# ninjaNIRS_TriggerBox_Rev1a.net
KiCad netlist of a schematic drawn in EAGLE
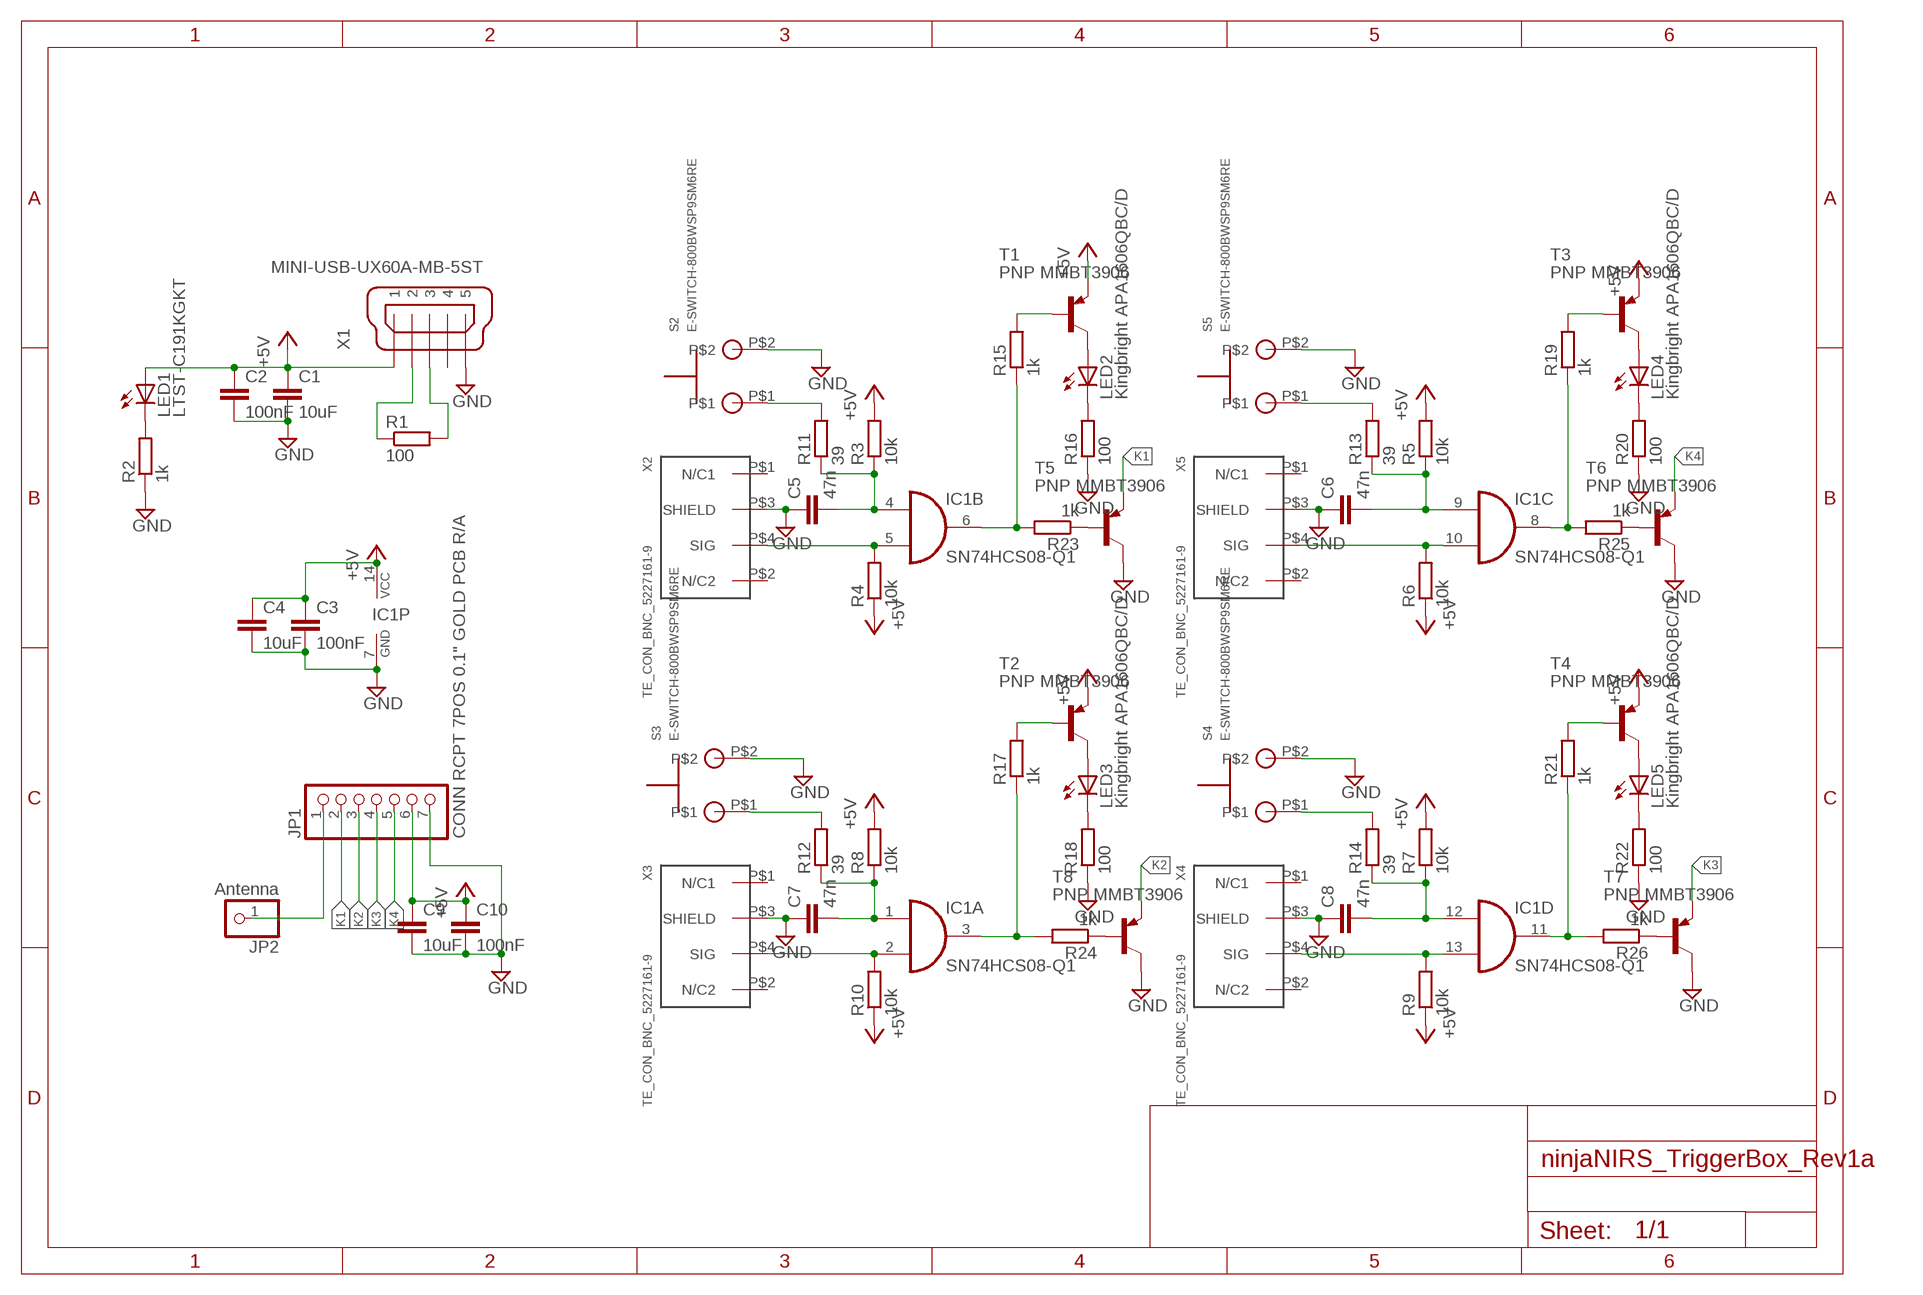
[diagram p0: schematic, sheet 1]

(export (version "E")
  (design (tool "Eeschema 10.0.6"))
  (components
    (comp (ref "C1")
      (value "10uF")
      (footprint "eagle-import:C1210")
      (libsource (lib "eagle-import") (part "C-EUC1210"))
    )
    (comp (ref "C2")
      (value "100nF")
      (footprint "eagle-import:C0805")
      (libsource (lib "eagle-import") (part "C-EUC0805"))
    )
    (comp (ref "C3")
      (value "100nF")
      (footprint "eagle-import:C0805")
      (libsource (lib "eagle-import") (part "C-EUC0805"))
    )
    (comp (ref "C4")
      (value "10uF")
      (footprint "eagle-import:C1210")
      (libsource (lib "eagle-import") (part "C-EUC1210"))
    )
    (comp (ref "C5")
      (value "47n")
      (footprint "eagle-import:C0805")
      (libsource (lib "eagle-import") (part "C-EUC0805"))
    )
    (comp (ref "C6")
      (value "47n")
      (footprint "eagle-import:C0805")
      (libsource (lib "eagle-import") (part "C-EUC0805"))
    )
    (comp (ref "C7")
      (value "47n")
      (footprint "eagle-import:C0805")
      (libsource (lib "eagle-import") (part "C-EUC0805"))
    )
    (comp (ref "C8")
      (value "47n")
      (footprint "eagle-import:C0805")
      (libsource (lib "eagle-import") (part "C-EUC0805"))
    )
    (comp (ref "C9")
      (value "10uF")
      (footprint "eagle-import:C1210")
      (libsource (lib "eagle-import") (part "C-EUC1210"))
    )
    (comp (ref "C10")
      (value "100nF")
      (footprint "eagle-import:C0805")
      (libsource (lib "eagle-import") (part "C-EUC0805"))
    )
    (comp (ref "IC1")
      (value "SN74HCS08-Q1")
      (footprint "eagle-import:SO14")
      (libsource (lib "eagle-import") (part "7408DHC"))
    )
    (comp (ref "JP1")
      (value "CONN RCPT 7POS 0.1\" GOLD PCB R/A")
      (footprint "eagle-import:1X07_90")
      (libsource (lib "eagle-import") (part "PINHD-1X7/90"))
    )
    (comp (ref "JP2")
      (value "Antenna")
      (footprint "eagle-import:1X01")
      (libsource (lib "eagle-import") (part "PINHD-1X1"))
    )
    (comp (ref "LED1")
      (value "LTST-C191KGKT")
      (footprint "eagle-import:CHIPLED_0603")
      (libsource (lib "eagle-import") (part "LEDCHIPLED_0603"))
    )
    (comp (ref "LED2")
      (value "Kingbright APA1606QBC/D")
      (footprint "eagle-import:CHIP-LED0603")
      (libsource (lib "eagle-import") (part "LEDCHIP-LED0603"))
    )
    (comp (ref "LED3")
      (value "Kingbright APA1606QBC/D")
      (footprint "eagle-import:CHIP-LED0603")
      (libsource (lib "eagle-import") (part "LEDCHIP-LED0603"))
    )
    (comp (ref "LED4")
      (value "Kingbright APA1606QBC/D")
      (footprint "eagle-import:CHIP-LED0603")
      (libsource (lib "eagle-import") (part "LEDCHIP-LED0603"))
    )
    (comp (ref "LED5")
      (value "Kingbright APA1606QBC/D")
      (footprint "eagle-import:CHIP-LED0603")
      (libsource (lib "eagle-import") (part "LEDCHIP-LED0603"))
    )
    (comp (ref "R1")
      (value "100")
      (footprint "eagle-import:R1206")
      (libsource (lib "eagle-import") (part "R-EU_R1206"))
    )
    (comp (ref "R2")
      (value "1k")
      (footprint "eagle-import:R1206")
      (libsource (lib "eagle-import") (part "R-EU_R1206"))
    )
    (comp (ref "R3")
      (value "10k")
      (footprint "eagle-import:R1206")
      (libsource (lib "eagle-import") (part "R-EU_R1206"))
    )
    (comp (ref "R4")
      (value "10k")
      (footprint "eagle-import:R1206")
      (libsource (lib "eagle-import") (part "R-EU_R1206"))
    )
    (comp (ref "R5")
      (value "10k")
      (footprint "eagle-import:R1206")
      (libsource (lib "eagle-import") (part "R-EU_R1206"))
    )
    (comp (ref "R6")
      (value "10k")
      (footprint "eagle-import:R1206")
      (libsource (lib "eagle-import") (part "R-EU_R1206"))
    )
    (comp (ref "R7")
      (value "10k")
      (footprint "eagle-import:R1206")
      (libsource (lib "eagle-import") (part "R-EU_R1206"))
    )
    (comp (ref "R8")
      (value "10k")
      (footprint "eagle-import:R1206")
      (libsource (lib "eagle-import") (part "R-EU_R1206"))
    )
    (comp (ref "R9")
      (value "10k")
      (footprint "eagle-import:R1206")
      (libsource (lib "eagle-import") (part "R-EU_R1206"))
    )
    (comp (ref "R10")
      (value "10k")
      (footprint "eagle-import:R1206")
      (libsource (lib "eagle-import") (part "R-EU_R1206"))
    )
    (comp (ref "R11")
      (value "39")
      (footprint "eagle-import:R1206")
      (libsource (lib "eagle-import") (part "R-EU_R1206"))
    )
    (comp (ref "R12")
      (value "39")
      (footprint "eagle-import:R1206")
      (libsource (lib "eagle-import") (part "R-EU_R1206"))
    )
    (comp (ref "R13")
      (value "39")
      (footprint "eagle-import:R1206")
      (libsource (lib "eagle-import") (part "R-EU_R1206"))
    )
    (comp (ref "R14")
      (value "39")
      (footprint "eagle-import:R1206")
      (libsource (lib "eagle-import") (part "R-EU_R1206"))
    )
    (comp (ref "R15")
      (value "1k")
      (footprint "eagle-import:R1206")
      (libsource (lib "eagle-import") (part "R-EU_R1206"))
    )
    (comp (ref "R16")
      (value "100")
      (footprint "eagle-import:R1206")
      (libsource (lib "eagle-import") (part "R-EU_R1206"))
    )
    (comp (ref "R17")
      (value "1k")
      (footprint "eagle-import:R1206")
      (libsource (lib "eagle-import") (part "R-EU_R1206"))
    )
    (comp (ref "R18")
      (value "100")
      (footprint "eagle-import:R1206")
      (libsource (lib "eagle-import") (part "R-EU_R1206"))
    )
    (comp (ref "R19")
      (value "1k")
      (footprint "eagle-import:R1206")
      (libsource (lib "eagle-import") (part "R-EU_R1206"))
    )
    (comp (ref "R20")
      (value "100")
      (footprint "eagle-import:R1206")
      (libsource (lib "eagle-import") (part "R-EU_R1206"))
    )
    (comp (ref "R21")
      (value "1k")
      (footprint "eagle-import:R1206")
      (libsource (lib "eagle-import") (part "R-EU_R1206"))
    )
    (comp (ref "R22")
      (value "100")
      (footprint "eagle-import:R1206")
      (libsource (lib "eagle-import") (part "R-EU_R1206"))
    )
    (comp (ref "R23")
      (value "1k")
      (footprint "eagle-import:R1206")
      (libsource (lib "eagle-import") (part "R-EU_R1206"))
    )
    (comp (ref "R24")
      (value "1k")
      (footprint "eagle-import:R1206")
      (libsource (lib "eagle-import") (part "R-EU_R1206"))
    )
    (comp (ref "R25")
      (value "1k")
      (footprint "eagle-import:R1206")
      (libsource (lib "eagle-import") (part "R-EU_R1206"))
    )
    (comp (ref "R26")
      (value "1k")
      (footprint "eagle-import:R1206")
      (libsource (lib "eagle-import") (part "R-EU_R1206"))
    )
    (comp (ref "S2")
      (value "E-SWITCH-800BWSP9SM6RE")
      (footprint "eagle-import:E-SWITCH_800BW")
      (libsource (lib "eagle-import") (part "E-SWITCH-800BWSP9SM6RE"))
    )
    (comp (ref "S3")
      (value "E-SWITCH-800BWSP9SM6RE")
      (footprint "eagle-import:E-SWITCH_800BW")
      (libsource (lib "eagle-import") (part "E-SWITCH-800BWSP9SM6RE"))
    )
    (comp (ref "S4")
      (value "E-SWITCH-800BWSP9SM6RE")
      (footprint "eagle-import:E-SWITCH_800BW")
      (libsource (lib "eagle-import") (part "E-SWITCH-800BWSP9SM6RE"))
    )
    (comp (ref "S5")
      (value "E-SWITCH-800BWSP9SM6RE")
      (footprint "eagle-import:E-SWITCH_800BW")
      (libsource (lib "eagle-import") (part "E-SWITCH-800BWSP9SM6RE"))
    )
    (comp (ref "T1")
      (value "PNP MMBT3906")
      (footprint "eagle-import:SOT23-BEC")
      (libsource (lib "eagle-import") (part "-PNP-SOT23-BECBC807-16"))
    )
    (comp (ref "T2")
      (value "PNP MMBT3906")
      (footprint "eagle-import:SOT23-BEC")
      (libsource (lib "eagle-import") (part "-PNP-SOT23-BECBC807-16"))
    )
    (comp (ref "T3")
      (value "PNP MMBT3906")
      (footprint "eagle-import:SOT23-BEC")
      (libsource (lib "eagle-import") (part "-PNP-SOT23-BECBC807-16"))
    )
    (comp (ref "T4")
      (value "PNP MMBT3906")
      (footprint "eagle-import:SOT23-BEC")
      (libsource (lib "eagle-import") (part "-PNP-SOT23-BECBC807-16"))
    )
    (comp (ref "T5")
      (value "PNP MMBT3906")
      (footprint "eagle-import:SOT23-BEC")
      (libsource (lib "eagle-import") (part "-PNP-SOT23-BECBC807-16"))
    )
    (comp (ref "T6")
      (value "PNP MMBT3906")
      (footprint "eagle-import:SOT23-BEC")
      (libsource (lib "eagle-import") (part "-PNP-SOT23-BECBC807-16"))
    )
    (comp (ref "T7")
      (value "PNP MMBT3906")
      (footprint "eagle-import:SOT23-BEC")
      (libsource (lib "eagle-import") (part "-PNP-SOT23-BECBC807-16"))
    )
    (comp (ref "T8")
      (value "PNP MMBT3906")
      (footprint "eagle-import:SOT23-BEC")
      (libsource (lib "eagle-import") (part "-PNP-SOT23-BECBC807-16"))
    )
    (comp (ref "X1")
      (value "MINI-USB-UX60A-MB-5ST")
      (footprint "eagle-import:UX60A-MB-5ST")
      (libsource (lib "eagle-import") (part "MINI-USB-UX60A-MB-5ST"))
    )
    (comp (ref "X2")
      (value "TE_CON_BNC_5227161-9")
      (footprint "eagle-import:TE_CON_BNC_5227161-9")
      (libsource (lib "eagle-import") (part "TE_CON_BNC_5227161-9"))
    )
    (comp (ref "X3")
      (value "TE_CON_BNC_5227161-9")
      (footprint "eagle-import:TE_CON_BNC_5227161-9")
      (libsource (lib "eagle-import") (part "TE_CON_BNC_5227161-9"))
    )
    (comp (ref "X4")
      (value "TE_CON_BNC_5227161-9")
      (footprint "eagle-import:TE_CON_BNC_5227161-9")
      (libsource (lib "eagle-import") (part "TE_CON_BNC_5227161-9"))
    )
    (comp (ref "X5")
      (value "TE_CON_BNC_5227161-9")
      (footprint "eagle-import:TE_CON_BNC_5227161-9")
      (libsource (lib "eagle-import") (part "TE_CON_BNC_5227161-9"))
    )
  )
  (nets
    (net (code "1") (name "+5V") (class "Default")
      (node (ref "C1") (pin "1") (pinfunction "1_1") (pintype "passive"))
      (node (ref "C10") (pin "1") (pinfunction "1_1") (pintype "passive"))
      (node (ref "C2") (pin "1") (pinfunction "1_1") (pintype "passive"))
      (node (ref "C3") (pin "1") (pinfunction "1_1") (pintype "passive"))
      (node (ref "C4") (pin "1") (pinfunction "1_1") (pintype "passive"))
      (node (ref "C9") (pin "1") (pinfunction "1_1") (pintype "passive"))
      (node (ref "IC1") (pin "14") (pinfunction "VCC_14") (pintype "power_in"))
      (node (ref "JP1") (pin "6") (pinfunction "6_6") (pintype "passive"))
      (node (ref "LED1") (pin "A") (pinfunction "A_A") (pintype "passive"))
      (node (ref "R10") (pin "1") (pinfunction "1_1") (pintype "passive"))
      (node (ref "R3") (pin "2") (pinfunction "2_2") (pintype "passive"))
      (node (ref "R4") (pin "1") (pinfunction "1_1") (pintype "passive"))
      (node (ref "R5") (pin "2") (pinfunction "2_2") (pintype "passive"))
      (node (ref "R6") (pin "1") (pinfunction "1_1") (pintype "passive"))
      (node (ref "R7") (pin "2") (pinfunction "2_2") (pintype "passive"))
      (node (ref "R8") (pin "2") (pinfunction "2_2") (pintype "passive"))
      (node (ref "R9") (pin "1") (pinfunction "1_1") (pintype "passive"))
      (node (ref "T1") (pin "E") (pinfunction "E_E") (pintype "passive"))
      (node (ref "T2") (pin "E") (pinfunction "E_E") (pintype "passive"))
      (node (ref "T3") (pin "E") (pinfunction "E_E") (pintype "passive"))
      (node (ref "T4") (pin "E") (pinfunction "E_E") (pintype "passive"))
      (node (ref "X1") (pin "1") (pinfunction "1_1") (pintype "input"))
    )
    (net (code "2") (name "GND") (class "Default")
      (node (ref "C1") (pin "2") (pinfunction "2_2") (pintype "passive"))
      (node (ref "C10") (pin "2") (pinfunction "2_2") (pintype "passive"))
      (node (ref "C2") (pin "2") (pinfunction "2_2") (pintype "passive"))
      (node (ref "C3") (pin "2") (pinfunction "2_2") (pintype "passive"))
      (node (ref "C4") (pin "2") (pinfunction "2_2") (pintype "passive"))
      (node (ref "C5") (pin "1") (pinfunction "1_1") (pintype "passive"))
      (node (ref "C6") (pin "1") (pinfunction "1_1") (pintype "passive"))
      (node (ref "C7") (pin "1") (pinfunction "1_1") (pintype "passive"))
      (node (ref "C8") (pin "1") (pinfunction "1_1") (pintype "passive"))
      (node (ref "C9") (pin "2") (pinfunction "2_2") (pintype "passive"))
      (node (ref "IC1") (pin "7") (pinfunction "GND_7") (pintype "power_in"))
      (node (ref "JP1") (pin "7") (pinfunction "7_7") (pintype "passive"))
      (node (ref "R16") (pin "1") (pinfunction "1_1") (pintype "passive"))
      (node (ref "R18") (pin "1") (pinfunction "1_1") (pintype "passive"))
      (node (ref "R2") (pin "1") (pinfunction "1_1") (pintype "passive"))
      (node (ref "R20") (pin "1") (pinfunction "1_1") (pintype "passive"))
      (node (ref "R22") (pin "1") (pinfunction "1_1") (pintype "passive"))
      (node (ref "S2") (pin "P$2") (pinfunction "P$2_P$2") (pintype "bidirectional"))
      (node (ref "S3") (pin "P$2") (pinfunction "P$2_P$2") (pintype "bidirectional"))
      (node (ref "S4") (pin "P$2") (pinfunction "P$2_P$2") (pintype "bidirectional"))
      (node (ref "S5") (pin "P$2") (pinfunction "P$2_P$2") (pintype "bidirectional"))
      (node (ref "T5") (pin "C") (pinfunction "C_C") (pintype "passive"))
      (node (ref "T6") (pin "C") (pinfunction "C_C") (pintype "passive"))
      (node (ref "T7") (pin "C") (pinfunction "C_C") (pintype "passive"))
      (node (ref "T8") (pin "C") (pinfunction "C_C") (pintype "passive"))
      (node (ref "X1") (pin "5") (pinfunction "5_5") (pintype "input"))
      (node (ref "X2") (pin "P$3") (pinfunction "SHIELD_P$3") (pintype "bidirectional"))
      (node (ref "X3") (pin "P$3") (pinfunction "SHIELD_P$3") (pintype "bidirectional"))
      (node (ref "X4") (pin "P$3") (pinfunction "SHIELD_P$3") (pintype "bidirectional"))
      (node (ref "X5") (pin "P$3") (pinfunction "SHIELD_P$3") (pintype "bidirectional"))
    )
    (net (code "3") (name "K1") (class "Default")
      (node (ref "JP1") (pin "2") (pinfunction "2_2") (pintype "passive"))
      (node (ref "T5") (pin "E") (pinfunction "E_E") (pintype "passive"))
    )
    (net (code "4") (name "K2") (class "Default")
      (node (ref "JP1") (pin "3") (pinfunction "3_3") (pintype "passive"))
      (node (ref "T8") (pin "E") (pinfunction "E_E") (pintype "passive"))
    )
    (net (code "5") (name "K3") (class "Default")
      (node (ref "JP1") (pin "4") (pinfunction "4_4") (pintype "passive"))
      (node (ref "T7") (pin "E") (pinfunction "E_E") (pintype "passive"))
    )
    (net (code "6") (name "K4") (class "Default")
      (node (ref "JP1") (pin "5") (pinfunction "5_5") (pintype "passive"))
      (node (ref "T6") (pin "E") (pinfunction "E_E") (pintype "passive"))
    )
    (net (code "7") (name "Net-(IC1A-I0)") (class "Default")
      (node (ref "C7") (pin "2") (pinfunction "2_2") (pintype "passive"))
      (node (ref "IC1") (pin "1") (pinfunction "I0_1") (pintype "input"))
      (node (ref "R12") (pin "1") (pinfunction "1_1") (pintype "passive"))
      (node (ref "R8") (pin "1") (pinfunction "1_1") (pintype "passive"))
    )
    (net (code "8") (name "Net-(IC1A-I1)") (class "Default")
      (node (ref "IC1") (pin "2") (pinfunction "I1_2") (pintype "input"))
      (node (ref "R10") (pin "2") (pinfunction "2_2") (pintype "passive"))
      (node (ref "X3") (pin "P$4") (pinfunction "SIG_P$4") (pintype "bidirectional"))
    )
    (net (code "9") (name "Net-(IC1A-O)") (class "Default")
      (node (ref "IC1") (pin "3") (pinfunction "O_3") (pintype "output"))
      (node (ref "R17") (pin "1") (pinfunction "1_1") (pintype "passive"))
      (node (ref "R24") (pin "2") (pinfunction "2_2") (pintype "passive"))
    )
    (net (code "10") (name "Net-(IC1B-I0)") (class "Default")
      (node (ref "C5") (pin "2") (pinfunction "2_2") (pintype "passive"))
      (node (ref "IC1") (pin "4") (pinfunction "I0_4") (pintype "input"))
      (node (ref "R11") (pin "1") (pinfunction "1_1") (pintype "passive"))
      (node (ref "R3") (pin "1") (pinfunction "1_1") (pintype "passive"))
    )
    (net (code "11") (name "Net-(IC1B-I1)") (class "Default")
      (node (ref "IC1") (pin "5") (pinfunction "I1_5") (pintype "input"))
      (node (ref "R4") (pin "2") (pinfunction "2_2") (pintype "passive"))
      (node (ref "X2") (pin "P$4") (pinfunction "SIG_P$4") (pintype "bidirectional"))
    )
    (net (code "12") (name "Net-(IC1B-O)") (class "Default")
      (node (ref "IC1") (pin "6") (pinfunction "O_6") (pintype "output"))
      (node (ref "R15") (pin "1") (pinfunction "1_1") (pintype "passive"))
      (node (ref "R23") (pin "2") (pinfunction "2_2") (pintype "passive"))
    )
    (net (code "13") (name "Net-(IC1C-I0)") (class "Default")
      (node (ref "C6") (pin "2") (pinfunction "2_2") (pintype "passive"))
      (node (ref "IC1") (pin "9") (pinfunction "I0_9") (pintype "input"))
      (node (ref "R13") (pin "1") (pinfunction "1_1") (pintype "passive"))
      (node (ref "R5") (pin "1") (pinfunction "1_1") (pintype "passive"))
    )
    (net (code "14") (name "Net-(IC1C-I1)") (class "Default")
      (node (ref "IC1") (pin "10") (pinfunction "I1_10") (pintype "input"))
      (node (ref "R6") (pin "2") (pinfunction "2_2") (pintype "passive"))
      (node (ref "X5") (pin "P$4") (pinfunction "SIG_P$4") (pintype "bidirectional"))
    )
    (net (code "15") (name "Net-(IC1C-O)") (class "Default")
      (node (ref "IC1") (pin "8") (pinfunction "O_8") (pintype "output"))
      (node (ref "R19") (pin "1") (pinfunction "1_1") (pintype "passive"))
      (node (ref "R25") (pin "2") (pinfunction "2_2") (pintype "passive"))
    )
    (net (code "16") (name "Net-(IC1D-I0)") (class "Default")
      (node (ref "C8") (pin "2") (pinfunction "2_2") (pintype "passive"))
      (node (ref "IC1") (pin "12") (pinfunction "I0_12") (pintype "input"))
      (node (ref "R14") (pin "1") (pinfunction "1_1") (pintype "passive"))
      (node (ref "R7") (pin "1") (pinfunction "1_1") (pintype "passive"))
    )
    (net (code "17") (name "Net-(IC1D-I1)") (class "Default")
      (node (ref "IC1") (pin "13") (pinfunction "I1_13") (pintype "input"))
      (node (ref "R9") (pin "2") (pinfunction "2_2") (pintype "passive"))
      (node (ref "X4") (pin "P$4") (pinfunction "SIG_P$4") (pintype "bidirectional"))
    )
    (net (code "18") (name "Net-(IC1D-O)") (class "Default")
      (node (ref "IC1") (pin "11") (pinfunction "O_11") (pintype "output"))
      (node (ref "R21") (pin "1") (pinfunction "1_1") (pintype "passive"))
      (node (ref "R26") (pin "2") (pinfunction "2_2") (pintype "passive"))
    )
    (net (code "19") (name "Net-(JP1-Pad1)") (class "Default")
      (node (ref "JP1") (pin "1") (pinfunction "1_1") (pintype "passive"))
      (node (ref "JP2") (pin "1") (pinfunction "1_1") (pintype "passive"))
    )
    (net (code "20") (name "Net-(LED1-PadC)") (class "Default")
      (node (ref "LED1") (pin "C") (pinfunction "C_C") (pintype "passive"))
      (node (ref "R2") (pin "2") (pinfunction "2_2") (pintype "passive"))
    )
    (net (code "21") (name "Net-(LED2-PadA)") (class "Default")
      (node (ref "LED2") (pin "A") (pinfunction "A_A") (pintype "passive"))
      (node (ref "T1") (pin "C") (pinfunction "C_C") (pintype "passive"))
    )
    (net (code "22") (name "Net-(LED2-PadC)") (class "Default")
      (node (ref "LED2") (pin "C") (pinfunction "C_C") (pintype "passive"))
      (node (ref "R16") (pin "2") (pinfunction "2_2") (pintype "passive"))
    )
    (net (code "23") (name "Net-(LED3-PadA)") (class "Default")
      (node (ref "LED3") (pin "A") (pinfunction "A_A") (pintype "passive"))
      (node (ref "T2") (pin "C") (pinfunction "C_C") (pintype "passive"))
    )
    (net (code "24") (name "Net-(LED3-PadC)") (class "Default")
      (node (ref "LED3") (pin "C") (pinfunction "C_C") (pintype "passive"))
      (node (ref "R18") (pin "2") (pinfunction "2_2") (pintype "passive"))
    )
    (net (code "25") (name "Net-(LED4-PadA)") (class "Default")
      (node (ref "LED4") (pin "A") (pinfunction "A_A") (pintype "passive"))
      (node (ref "T3") (pin "C") (pinfunction "C_C") (pintype "passive"))
    )
    (net (code "26") (name "Net-(LED4-PadC)") (class "Default")
      (node (ref "LED4") (pin "C") (pinfunction "C_C") (pintype "passive"))
      (node (ref "R20") (pin "2") (pinfunction "2_2") (pintype "passive"))
    )
    (net (code "27") (name "Net-(LED5-PadA)") (class "Default")
      (node (ref "LED5") (pin "A") (pinfunction "A_A") (pintype "passive"))
      (node (ref "T4") (pin "C") (pinfunction "C_C") (pintype "passive"))
    )
    (net (code "28") (name "Net-(LED5-PadC)") (class "Default")
      (node (ref "LED5") (pin "C") (pinfunction "C_C") (pintype "passive"))
      (node (ref "R22") (pin "2") (pinfunction "2_2") (pintype "passive"))
    )
    (net (code "29") (name "Net-(R1-Pad1)") (class "Default")
      (node (ref "R1") (pin "1") (pinfunction "1_1") (pintype "passive"))
      (node (ref "X1") (pin "2") (pinfunction "2_2") (pintype "input"))
    )
    (net (code "30") (name "Net-(R1-Pad2)") (class "Default")
      (node (ref "R1") (pin "2") (pinfunction "2_2") (pintype "passive"))
      (node (ref "X1") (pin "3") (pinfunction "3_3") (pintype "input"))
    )
    (net (code "31") (name "Net-(R11-Pad2)") (class "Default")
      (node (ref "R11") (pin "2") (pinfunction "2_2") (pintype "passive"))
      (node (ref "S2") (pin "P$1") (pinfunction "P$1_P$1") (pintype "bidirectional"))
    )
    (net (code "32") (name "Net-(R12-Pad2)") (class "Default")
      (node (ref "R12") (pin "2") (pinfunction "2_2") (pintype "passive"))
      (node (ref "S3") (pin "P$1") (pinfunction "P$1_P$1") (pintype "bidirectional"))
    )
    (net (code "33") (name "Net-(R13-Pad2)") (class "Default")
      (node (ref "R13") (pin "2") (pinfunction "2_2") (pintype "passive"))
      (node (ref "S5") (pin "P$1") (pinfunction "P$1_P$1") (pintype "bidirectional"))
    )
    (net (code "34") (name "Net-(R14-Pad2)") (class "Default")
      (node (ref "R14") (pin "2") (pinfunction "2_2") (pintype "passive"))
      (node (ref "S4") (pin "P$1") (pinfunction "P$1_P$1") (pintype "bidirectional"))
    )
    (net (code "35") (name "Net-(R15-Pad2)") (class "Default")
      (node (ref "R15") (pin "2") (pinfunction "2_2") (pintype "passive"))
      (node (ref "T1") (pin "B") (pinfunction "B_B") (pintype "passive"))
    )
    (net (code "36") (name "Net-(R17-Pad2)") (class "Default")
      (node (ref "R17") (pin "2") (pinfunction "2_2") (pintype "passive"))
      (node (ref "T2") (pin "B") (pinfunction "B_B") (pintype "passive"))
    )
    (net (code "37") (name "Net-(R19-Pad2)") (class "Default")
      (node (ref "R19") (pin "2") (pinfunction "2_2") (pintype "passive"))
      (node (ref "T3") (pin "B") (pinfunction "B_B") (pintype "passive"))
    )
    (net (code "38") (name "Net-(R21-Pad2)") (class "Default")
      (node (ref "R21") (pin "2") (pinfunction "2_2") (pintype "passive"))
      (node (ref "T4") (pin "B") (pinfunction "B_B") (pintype "passive"))
    )
    (net (code "39") (name "Net-(R23-Pad1)") (class "Default")
      (node (ref "R23") (pin "1") (pinfunction "1_1") (pintype "passive"))
      (node (ref "T5") (pin "B") (pinfunction "B_B") (pintype "passive"))
    )
    (net (code "40") (name "Net-(R24-Pad1)") (class "Default")
      (node (ref "R24") (pin "1") (pinfunction "1_1") (pintype "passive"))
      (node (ref "T8") (pin "B") (pinfunction "B_B") (pintype "passive"))
    )
    (net (code "41") (name "Net-(R25-Pad1)") (class "Default")
      (node (ref "R25") (pin "1") (pinfunction "1_1") (pintype "passive"))
      (node (ref "T6") (pin "B") (pinfunction "B_B") (pintype "passive"))
    )
    (net (code "42") (name "Net-(R26-Pad1)") (class "Default")
      (node (ref "R26") (pin "1") (pinfunction "1_1") (pintype "passive"))
      (node (ref "T7") (pin "B") (pinfunction "B_B") (pintype "passive"))
    )
    (net (code "43") (name "unconnected-(X1-Pad4)") (class "Default")
      (node (ref "X1") (pin "4") (pinfunction "4_4") (pintype "input"))
    )
    (net (code "44") (name "unconnected-(X2-N{slash}C1-PadP$1)") (class "Default")
      (node (ref "X2") (pin "P$1") (pinfunction "N/C1_P$1") (pintype "bidirectional"))
    )
    (net (code "45") (name "unconnected-(X2-N{slash}C2-PadP$2)") (class "Default")
      (node (ref "X2") (pin "P$2") (pinfunction "N/C2_P$2") (pintype "bidirectional"))
    )
    (net (code "46") (name "unconnected-(X3-N{slash}C1-PadP$1)") (class "Default")
      (node (ref "X3") (pin "P$1") (pinfunction "N/C1_P$1") (pintype "bidirectional"))
    )
    (net (code "47") (name "unconnected-(X3-N{slash}C2-PadP$2)") (class "Default")
      (node (ref "X3") (pin "P$2") (pinfunction "N/C2_P$2") (pintype "bidirectional"))
    )
    (net (code "48") (name "unconnected-(X4-N{slash}C1-PadP$1)") (class "Default")
      (node (ref "X4") (pin "P$1") (pinfunction "N/C1_P$1") (pintype "bidirectional"))
    )
    (net (code "49") (name "unconnected-(X4-N{slash}C2-PadP$2)") (class "Default")
      (node (ref "X4") (pin "P$2") (pinfunction "N/C2_P$2") (pintype "bidirectional"))
    )
    (net (code "50") (name "unconnected-(X5-N{slash}C1-PadP$1)") (class "Default")
      (node (ref "X5") (pin "P$1") (pinfunction "N/C1_P$1") (pintype "bidirectional"))
    )
    (net (code "51") (name "unconnected-(X5-N{slash}C2-PadP$2)") (class "Default")
      (node (ref "X5") (pin "P$2") (pinfunction "N/C2_P$2") (pintype "bidirectional"))
    )
  )
)
